# pc_healthypi_move_nRF5340_v4.net
KiCad netlist of a schematic drawn in EAGLE
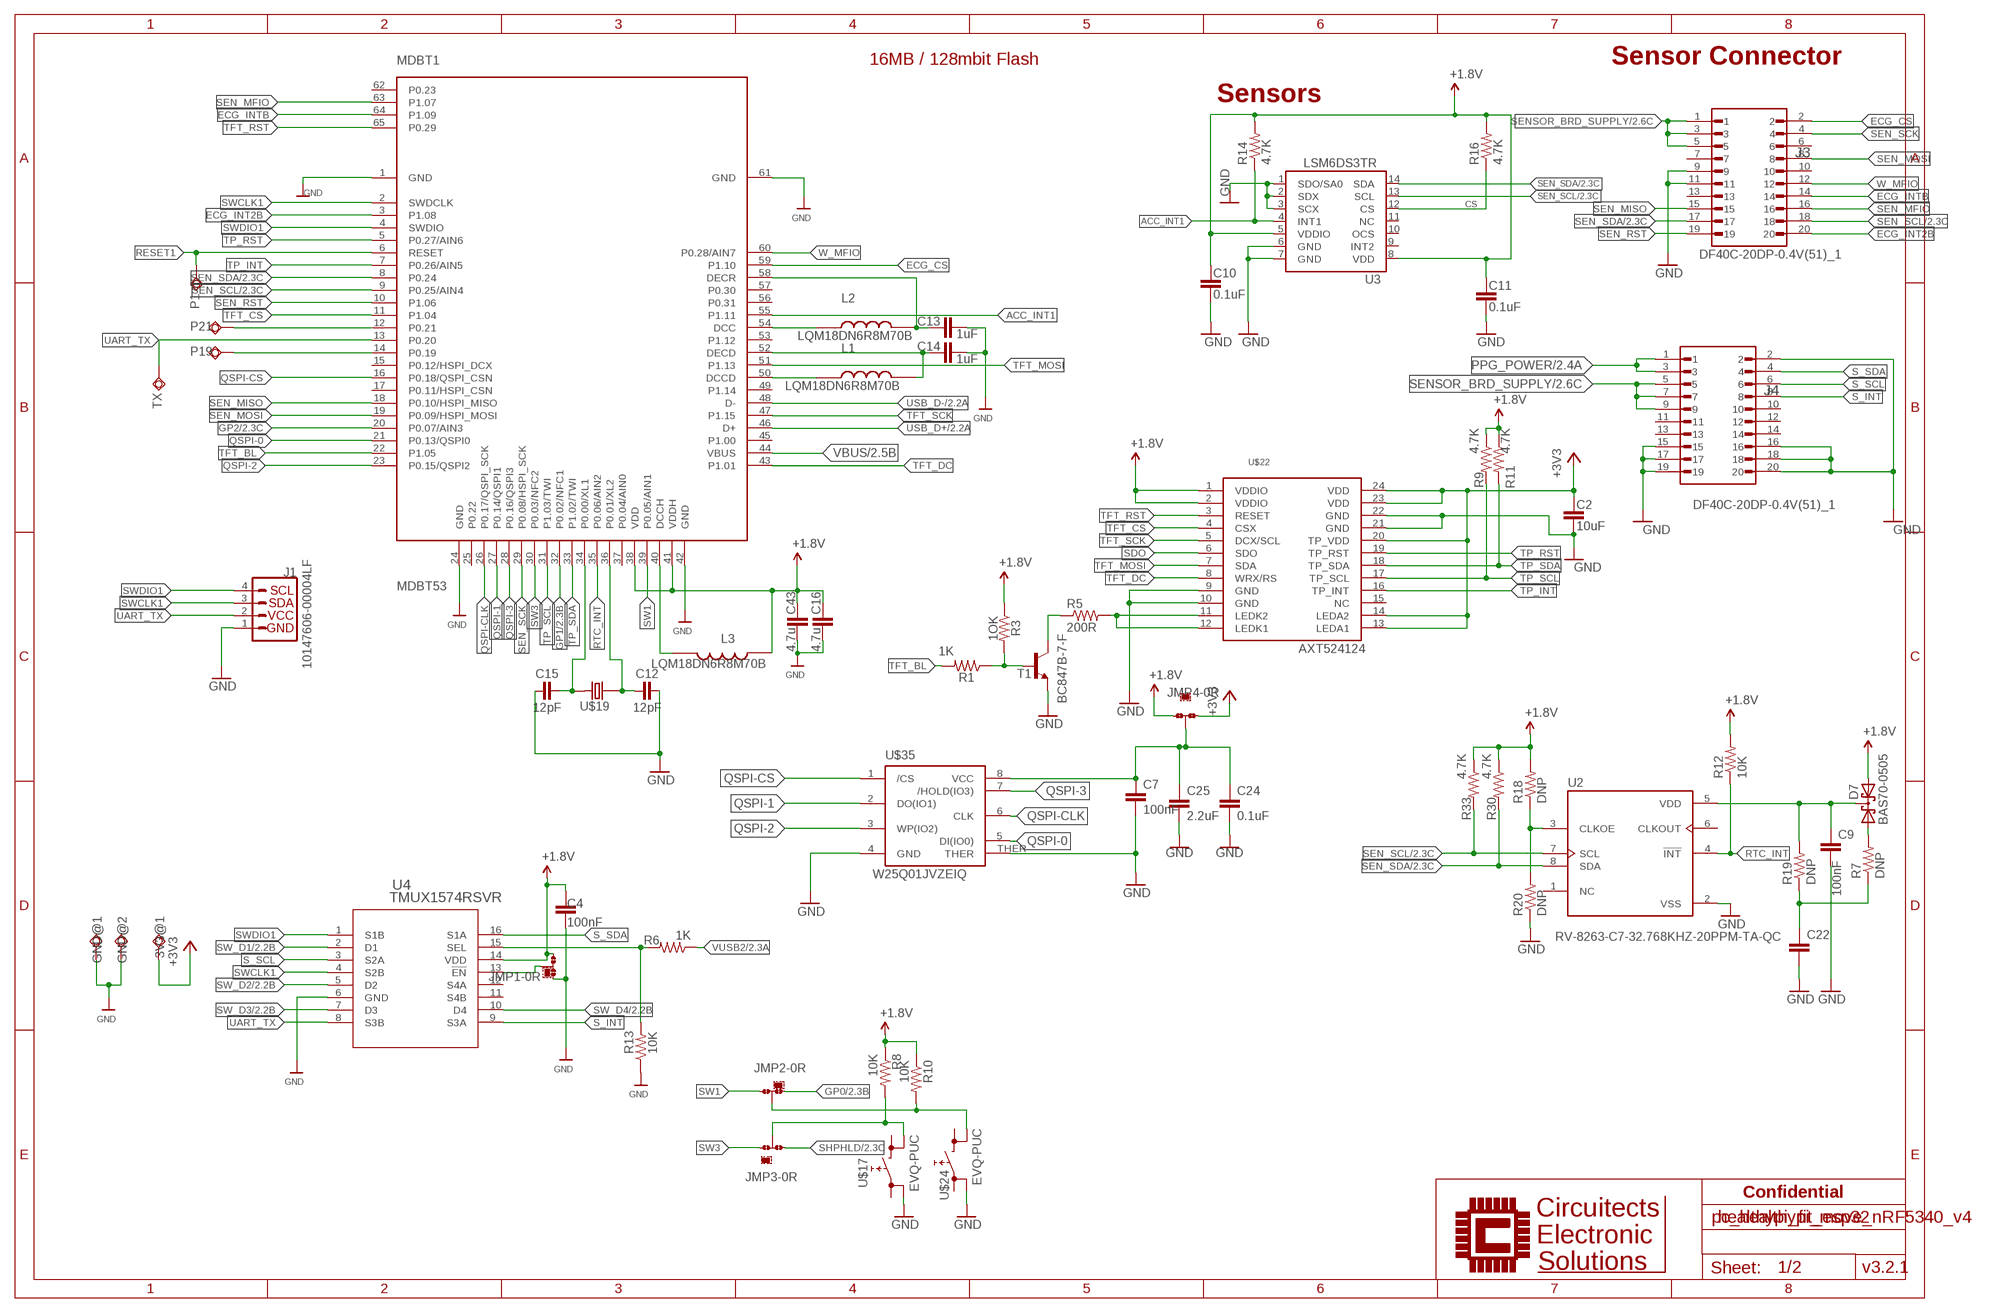
[diagram p0: schematic, sheet 1]
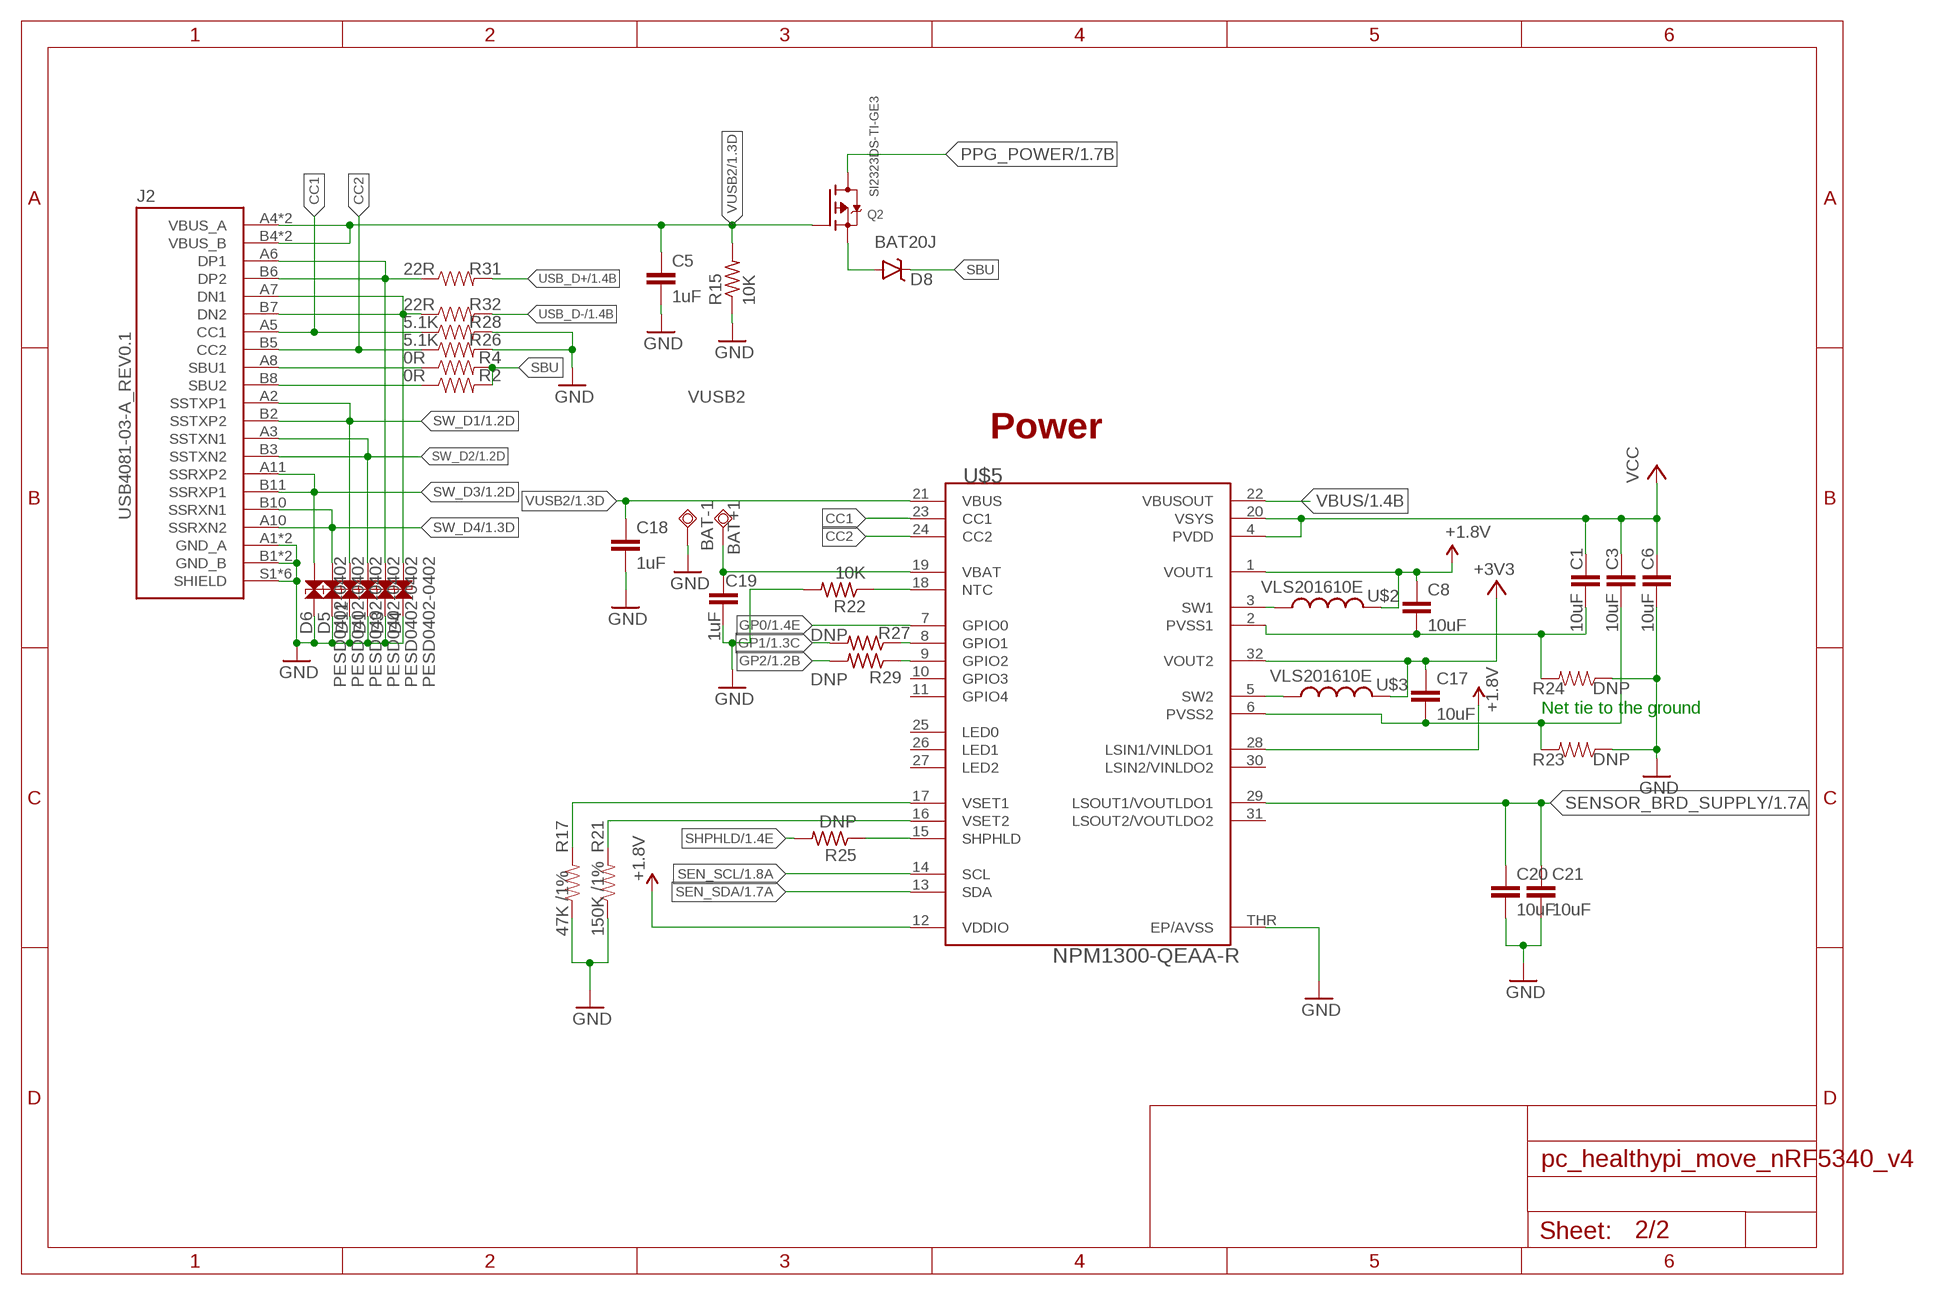
[diagram p1: schematic, sheet 2]

(export (version "E")
  (design (tool "Eeschema 10.0.6"))
  (components
    (comp (ref "BAT+1")
      (value "TPSQTP13SQ")
      (footprint "eagle-import:TP13SQ")
      (libsource (lib "eagle-import") (part "TPSQTP13SQ"))
    )
    (comp (ref "BAT-1")
      (value "TPSQTP13SQ")
      (footprint "eagle-import:TP13SQ")
      (libsource (lib "eagle-import") (part "TPSQTP13SQ"))
    )
    (comp (ref "C1")
      (value "10uF")
      (footprint "eagle-import:0402-TIGHT")
      (libsource (lib "eagle-import") (part "2.2UF-0402_TIGHT-10V-10%-X5R"))
    )
    (comp (ref "C3")
      (value "10uF")
      (footprint "eagle-import:0402-TIGHT")
      (libsource (lib "eagle-import") (part "2.2UF-0402_TIGHT-10V-10%-X5R"))
    )
    (comp (ref "C5")
      (value "1uF")
      (footprint "eagle-import:0402-TIGHT")
      (libsource (lib "eagle-import") (part "2.2UF-0402_TIGHT-10V-10%-X5R"))
    )
    (comp (ref "C6")
      (value "10uF")
      (footprint "eagle-import:0402-TIGHT")
      (libsource (lib "eagle-import") (part "2.2UF-0402_TIGHT-10V-10%-X5R"))
    )
    (comp (ref "C8")
      (value "10uF")
      (footprint "eagle-import:0402-TIGHT")
      (libsource (lib "eagle-import") (part "2.2UF-0402_TIGHT-10V-10%-X5R"))
    )
    (comp (ref "C17")
      (value "10uF")
      (footprint "eagle-import:0402-TIGHT")
      (libsource (lib "eagle-import") (part "2.2UF-0402_TIGHT-10V-10%-X5R"))
    )
    (comp (ref "C18")
      (value "1uF")
      (footprint "eagle-import:0402-TIGHT")
      (libsource (lib "eagle-import") (part "2.2UF-0402_TIGHT-10V-10%-X5R"))
    )
    (comp (ref "C19")
      (value "1uF")
      (footprint "eagle-import:0402-TIGHT")
      (libsource (lib "eagle-import") (part "2.2UF-0402_TIGHT-10V-10%-X5R"))
    )
    (comp (ref "C20")
      (value "10uF")
      (footprint "eagle-import:0402-TIGHT")
      (libsource (lib "eagle-import") (part "2.2UF-0402_TIGHT-10V-10%-X5R"))
    )
    (comp (ref "C21")
      (value "10uF")
      (footprint "eagle-import:0402-TIGHT")
      (libsource (lib "eagle-import") (part "2.2UF-0402_TIGHT-10V-10%-X5R"))
    )
    (comp (ref "D1")
      (value "PESD0402-0402")
      (footprint "eagle-import:0402")
      (fields
        (field (name "DIGIKEY_PART") "PESD0402-140CT-ND")
        (field (name "MOUSE_PART") "650-PESD0402-140")
      )
      (libsource (lib "eagle-import") (part "PESD0402-0402"))
    )
    (comp (ref "D3")
      (value "PESD0402-0402")
      (footprint "eagle-import:0402")
      (fields
        (field (name "DIGIKEY_PART") "PESD0402-140CT-ND")
        (field (name "MOUSE_PART") "650-PESD0402-140")
      )
      (libsource (lib "eagle-import") (part "PESD0402-0402"))
    )
    (comp (ref "D4")
      (value "PESD0402-0402")
      (footprint "eagle-import:0402")
      (fields
        (field (name "DIGIKEY_PART") "PESD0402-140CT-ND")
        (field (name "MOUSE_PART") "650-PESD0402-140")
      )
      (libsource (lib "eagle-import") (part "PESD0402-0402"))
    )
    (comp (ref "D5")
      (value "PESD0402-0402")
      (footprint "eagle-import:0402")
      (fields
        (field (name "DIGIKEY_PART") "PESD0402-140CT-ND")
        (field (name "MOUSE_PART") "650-PESD0402-140")
      )
      (libsource (lib "eagle-import") (part "PESD0402-0402"))
    )
    (comp (ref "D6")
      (value "PESD0402-0402")
      (footprint "eagle-import:0402")
      (fields
        (field (name "DIGIKEY_PART") "PESD0402-140CT-ND")
        (field (name "MOUSE_PART") "650-PESD0402-140")
      )
      (libsource (lib "eagle-import") (part "PESD0402-0402"))
    )
    (comp (ref "D8")
      (value "BAT20J")
      (footprint "eagle-import:SOD-323")
      (libsource (lib "eagle-import") (part "DIODE-SCHOTTKY-BAT20J"))
    )
    (comp (ref "D11")
      (value "PESD0402-0402")
      (footprint "eagle-import:0402")
      (fields
        (field (name "DIGIKEY_PART") "PESD0402-140CT-ND")
        (field (name "MOUSE_PART") "650-PESD0402-140")
      )
      (libsource (lib "eagle-import") (part "PESD0402-0402"))
    )
    (comp (ref "J2")
      (value "USB4081-03-A_REV0.1")
      (footprint "eagle-import:GCT_USB4081-03-A_REV0.1")
      (fields (field (name "MF") "Global Connector Technology") (field (name "MP") "USB4081-03-A"))
      (libsource (lib "eagle-import") (part "USB4081-03-A_REV0.1"))
    )
    (comp (ref "Q2")
      (value "SI2323DS-TI-GE3")
      (footprint "eagle-import:SOT23-R")
      (libsource (lib "eagle-import") (part "MOSFET-P"))
    )
    (comp (ref "R2")
      (value "0R")
      (footprint "eagle-import:0402-RES")
      (libsource (lib "eagle-import") (part "RESISTOR0402-RES"))
    )
    (comp (ref "R4")
      (value "0R")
      (footprint "eagle-import:0402-RES")
      (libsource (lib "eagle-import") (part "RESISTOR0402-RES"))
    )
    (comp (ref "R15")
      (value "10K")
      (footprint "eagle-import:R0402")
      (libsource (lib "eagle-import") (part "R-US_R0402"))
    )
    (comp (ref "R17")
      (value "47K /1%")
      (footprint "eagle-import:0402-RES")
      (libsource (lib "eagle-import") (part "RESISTOR0402-RES"))
    )
    (comp (ref "R21")
      (value "150K /1%")
      (footprint "eagle-import:0402-RES")
      (libsource (lib "eagle-import") (part "RESISTOR0402-RES"))
    )
    (comp (ref "R22")
      (value "10K")
      (footprint "eagle-import:R0402")
      (libsource (lib "eagle-import") (part "R-US_R0402"))
    )
    (comp (ref "R23")
      (value "DNP")
      (footprint "eagle-import:0402-RES")
      (libsource (lib "eagle-import") (part "RESISTOR0402-RES"))
    )
    (comp (ref "R24")
      (value "DNP")
      (footprint "eagle-import:0402-RES")
      (libsource (lib "eagle-import") (part "RESISTOR0402-RES"))
    )
    (comp (ref "R25")
      (value "DNP")
      (footprint "eagle-import:R0402")
      (libsource (lib "eagle-import") (part "R-US_R0402"))
    )
    (comp (ref "R26")
      (value "5.1K")
      (footprint "eagle-import:0402-RES")
      (libsource (lib "eagle-import") (part "RESISTOR0402-RES"))
    )
    (comp (ref "R27")
      (value "DNP")
      (footprint "eagle-import:R0402")
      (libsource (lib "eagle-import") (part "R-US_R0402"))
    )
    (comp (ref "R28")
      (value "5.1K")
      (footprint "eagle-import:0402-RES")
      (libsource (lib "eagle-import") (part "RESISTOR0402-RES"))
    )
    (comp (ref "R29")
      (value "DNP")
      (footprint "eagle-import:R0402")
      (libsource (lib "eagle-import") (part "R-US_R0402"))
    )
    (comp (ref "R31")
      (value "22R")
      (footprint "eagle-import:0402-RES")
      (libsource (lib "eagle-import") (part "RESISTOR0402-RES"))
    )
    (comp (ref "R32")
      (value "22R")
      (footprint "eagle-import:0402-RES")
      (libsource (lib "eagle-import") (part "RESISTOR0402-RES"))
    )
    (comp (ref "U$2")
      (value "VLS201610E")
      (footprint "eagle-import:VLS201610E")
      (libsource (lib "eagle-import") (part "VLS201610E"))
    )
    (comp (ref "U$3")
      (value "VLS201610E")
      (footprint "eagle-import:VLS201610E")
      (libsource (lib "eagle-import") (part "VLS201610E"))
    )
    (comp (ref "U$5")
      (value "NPM1300-QEAA-R")
      (footprint "eagle-import:PWQFN-32")
      (libsource (lib "eagle-import") (part "NPM1300-QEAA-R"))
    )
    (comp (ref "3V3@1")
      (value "TPSQTP13SQ")
      (footprint "eagle-import:TP13SQ")
      (libsource (lib "eagle-import") (part "TPSQTP13SQ"))
    )
    (comp (ref "C2")
      (value "10uF")
      (footprint "eagle-import:0603@1")
      (libsource (lib "eagle-import") (part "0.1UF-0603-100V-10%"))
    )
    (comp (ref "C4")
      (value "100nF")
      (footprint "eagle-import:0402-TIGHT")
      (libsource (lib "eagle-import") (part "2.2UF-0402_TIGHT-10V-10%-X5R"))
    )
    (comp (ref "C7")
      (value "100nF")
      (footprint "eagle-import:C0402")
      (libsource (lib "eagle-import") (part "C-EUC0402"))
    )
    (comp (ref "C9")
      (value "100nF")
      (footprint "eagle-import:C0402")
      (libsource (lib "eagle-import") (part "C-EUC0402"))
    )
    (comp (ref "C10")
      (value "0.1uF")
      (footprint "eagle-import:0402-TIGHT")
      (libsource (lib "eagle-import") (part "0.1UF-0402T-6.3V-10%-X7R"))
    )
    (comp (ref "C11")
      (value "0.1uF")
      (footprint "eagle-import:0402-TIGHT")
      (libsource (lib "eagle-import") (part "0.1UF-0402T-6.3V-10%-X7R"))
    )
    (comp (ref "C12")
      (value "12pF")
      (footprint "eagle-import:C0402")
      (libsource (lib "eagle-import") (part "CAPACITORS-0402"))
    )
    (comp (ref "C13")
      (value "1uF")
      (footprint "eagle-import:0402-TIGHT")
      (libsource (lib "eagle-import") (part "2.2UF-0402_TIGHT-10V-10%-X5R"))
    )
    (comp (ref "C14")
      (value "1uF")
      (footprint "eagle-import:0402-TIGHT")
      (libsource (lib "eagle-import") (part "2.2UF-0402_TIGHT-10V-10%-X5R"))
    )
    (comp (ref "C15")
      (value "12pF")
      (footprint "eagle-import:C0402")
      (libsource (lib "eagle-import") (part "CAPACITORS-0402"))
    )
    (comp (ref "C16")
      (value "4.7u")
      (footprint "eagle-import:C0402")
      (libsource (lib "eagle-import") (part "C-EUC0402"))
    )
    (comp (ref "C22")
      (value "C-EUC1210")
      (footprint "eagle-import:C1210")
      (libsource (lib "eagle-import") (part "C-EUC1210"))
    )
    (comp (ref "C24")
      (value "0.1uF")
      (footprint "eagle-import:0402-TIGHT")
      (libsource (lib "eagle-import") (part "0.1UF-0402T-6.3V-10%-X7R"))
    )
    (comp (ref "C25")
      (value "2.2uF")
      (footprint "eagle-import:0402-TIGHT")
      (libsource (lib "eagle-import") (part "2.2UF-0402_TIGHT-10V-10%-X5R"))
    )
    (comp (ref "C43")
      (value "4.7u")
      (footprint "eagle-import:C0402")
      (libsource (lib "eagle-import") (part "C-EUC0402"))
    )
    (comp (ref "D7")
      (value "BAS70-0505")
      (footprint "eagle-import:SOT23")
      (fields (field (name "MF") "Diotec") (field (name "MP") "BAS70-05"))
      (libsource (lib "eagle-import") (part "BAS70-0505"))
    )
    (comp (ref "GND@1")
      (value "TPSQTP13SQ")
      (footprint "eagle-import:TP13SQ")
      (libsource (lib "eagle-import") (part "TPSQTP13SQ"))
    )
    (comp (ref "GND@2")
      (value "TPSQTP13SQ")
      (footprint "eagle-import:TP13SQ")
      (libsource (lib "eagle-import") (part "TPSQTP13SQ"))
    )
    (comp (ref "J1")
      (value "10147606-00004LF")
      (footprint "eagle-import:JST04_1MM_RA")
      (libsource (lib "eagle-import") (part "QWIIC_CONNECTORJS-1MM"))
    )
    (comp (ref "J3")
      (value "DF40C-20DP-0.4V(51)_1")
      (footprint "eagle-import:HRS_DF40C-20DP-0.4V(51)")
      (fields (field (name "MANUFACTURER") "Hirose Electric"))
      (libsource (lib "eagle-import") (part "DF40C-20DP-0.4V(51)_1"))
    )
    (comp (ref "J4")
      (value "DF40C-20DP-0.4V(51)_1")
      (footprint "eagle-import:HRS_DF40C-20DP-0.4V(51)")
      (fields (field (name "MANUFACTURER") "Hirose Electric"))
      (libsource (lib "eagle-import") (part "DF40C-20DP-0.4V(51)_1"))
    )
    (comp (ref "JMP1")
      (value "0R-JUMPB")
      (footprint "eagle-import:B0R-JMP")
      (libsource (lib "eagle-import") (part "0R-JUMPB"))
    )
    (comp (ref "JMP2")
      (value "0R-JUMPB")
      (footprint "eagle-import:B0R-JMP")
      (libsource (lib "eagle-import") (part "0R-JUMPB"))
    )
    (comp (ref "JMP3")
      (value "0R-JUMPB")
      (footprint "eagle-import:B0R-JMP")
      (libsource (lib "eagle-import") (part "0R-JUMPB"))
    )
    (comp (ref "JMP4")
      (value "0R-JUMPB")
      (footprint "eagle-import:B0R-JMP")
      (libsource (lib "eagle-import") (part "0R-JUMPB"))
    )
    (comp (ref "L1")
      (value "LQM18DN6R8M70B")
      (footprint "eagle-import:INDC1608X95N")
      (fields (field (name "MF") "Murata"))
      (libsource (lib "eagle-import") (part "LQM18DN6R8M70B"))
    )
    (comp (ref "L2")
      (value "LQM18DN6R8M70B")
      (footprint "eagle-import:INDC1608X95N")
      (fields (field (name "MF") "Murata"))
      (libsource (lib "eagle-import") (part "LQM18DN6R8M70B"))
    )
    (comp (ref "L3")
      (value "LQM18DN6R8M70B")
      (footprint "eagle-import:INDC1608X95N")
      (fields (field (name "MF") "Murata"))
      (libsource (lib "eagle-import") (part "LQM18DN6R8M70B"))
    )
    (comp (ref "MDBT1")
      (value "MDBT53")
      (footprint "eagle-import:MDBT53")
      (libsource (lib "eagle-import") (part "MDBT53"))
    )
    (comp (ref "P1")
      (value "TPSQTP13SQ")
      (footprint "eagle-import:TP13SQ")
      (libsource (lib "eagle-import") (part "TPSQTP13SQ"))
    )
    (comp (ref "P19")
      (value "TPSQTP13SQ")
      (footprint "eagle-import:TP13SQ")
      (libsource (lib "eagle-import") (part "TPSQTP13SQ"))
    )
    (comp (ref "P21")
      (value "TPSQTP13SQ")
      (footprint "eagle-import:TP13SQ")
      (libsource (lib "eagle-import") (part "TPSQTP13SQ"))
    )
    (comp (ref "R1")
      (value "200")
      (footprint "eagle-import:R0402")
      (libsource (lib "eagle-import") (part "R-US_R0402"))
    )
    (comp (ref "R3")
      (value "200")
      (footprint "eagle-import:R0402")
      (libsource (lib "eagle-import") (part "R-US_R0402"))
    )
    (comp (ref "R5")
      (value "200R")
      (footprint "eagle-import:R0402")
      (libsource (lib "eagle-import") (part "R-US_R0402"))
    )
    (comp (ref "R6")
      (value "1K")
      (footprint "eagle-import:0402-RES")
      (libsource (lib "eagle-import") (part "RESISTOR0402-RES"))
    )
    (comp (ref "R7")
      (value "DNP")
      (footprint "eagle-import:R0402")
      (libsource (lib "eagle-import") (part "R-US_R0402"))
    )
    (comp (ref "R8")
      (value "10K")
      (footprint "eagle-import:R0402")
      (libsource (lib "eagle-import") (part "R-US_R0402"))
    )
    (comp (ref "R9")
      (value "4.7K")
      (footprint "eagle-import:R0402")
      (libsource (lib "eagle-import") (part "R-US_R0402"))
    )
    (comp (ref "R10")
      (value "10K")
      (footprint "eagle-import:R0402")
      (libsource (lib "eagle-import") (part "R-US_R0402"))
    )
    (comp (ref "R11")
      (value "4.7K")
      (footprint "eagle-import:R0402")
      (libsource (lib "eagle-import") (part "R-US_R0402"))
    )
    (comp (ref "R12")
      (value "10K")
      (footprint "eagle-import:R0402")
      (libsource (lib "eagle-import") (part "R-US_R0402"))
    )
    (comp (ref "R13")
      (value "10K")
      (footprint "eagle-import:R0402")
      (libsource (lib "eagle-import") (part "R-US_R0402"))
    )
    (comp (ref "R14")
      (value "4.7K")
      (footprint "eagle-import:R0402")
      (libsource (lib "eagle-import") (part "R-US_R0402"))
    )
    (comp (ref "R16")
      (value "4.7K")
      (footprint "eagle-import:R0402")
      (libsource (lib "eagle-import") (part "R-US_R0402"))
    )
    (comp (ref "R18")
      (value "DNP")
      (footprint "eagle-import:R0402")
      (libsource (lib "eagle-import") (part "R-US_R0402"))
    )
    (comp (ref "R19")
      (value "DNP")
      (footprint "eagle-import:R0402")
      (libsource (lib "eagle-import") (part "R-US_R0402"))
    )
    (comp (ref "R20")
      (value "DNP")
      (footprint "eagle-import:R0402")
      (libsource (lib "eagle-import") (part "R-US_R0402"))
    )
    (comp (ref "R30")
      (value "4.7K")
      (footprint "eagle-import:R0402")
      (libsource (lib "eagle-import") (part "R-US_R0402"))
    )
    (comp (ref "R33")
      (value "4.7K")
      (footprint "eagle-import:R0402")
      (libsource (lib "eagle-import") (part "R-US_R0402"))
    )
    (comp (ref "T1")
      (value "BC847B-7-F")
      (footprint "eagle-import:SOT23-BEC")
      (libsource (lib "eagle-import") (part "-NPN-SOT23-BECMMBT2222ALT1"))
    )
    (comp (ref "TX")
      (value "TPSQTP13SQ")
      (footprint "eagle-import:TP13SQ")
      (libsource (lib "eagle-import") (part "TPSQTP13SQ"))
    )
    (comp (ref "U$17")
      (value "EVQ-PUC")
      (footprint "eagle-import:EVQ-PUC")
      (libsource (lib "eagle-import") (part "EVQ-PUC"))
    )
    (comp (ref "U$19")
      (value "520-327-12.5-34B(32.768KHZ)")
      (footprint "eagle-import:ECX-31B")
      (libsource (lib "eagle-import") (part "ECS-X-34B"))
    )
    (comp (ref "U$22")
      (value "AXT524124")
      (footprint "eagle-import:AXT524124")
      (libsource (lib "eagle-import") (part "AXT524124"))
    )
    (comp (ref "U$24")
      (value "EVQ-PUC")
      (footprint "eagle-import:EVQ-PUC")
      (libsource (lib "eagle-import") (part "EVQ-PUC"))
    )
    (comp (ref "U$35")
      (value "W25Q01JVZEIQ")
      (footprint "eagle-import:WSON-08")
      (libsource (lib "eagle-import") (part "W25N01GVZEIG"))
    )
    (comp (ref "U2")
      (value "RV-8263-C7-32.768KHZ-20PPM-TA-QC")
      (footprint "eagle-import:IC_RV-8263-C7-32.768KHZ-20PPM-TA-QC")
      (fields (field (name "MF") "Micro Crystal"))
      (libsource (lib "eagle-import") (part "RV-8263-C7-32.768KHZ-20PPM-TA-QC"))
    )
    (comp (ref "U3")
      (value "LSM6DS3TR")
      (footprint "eagle-import:LGA14L")
      (libsource (lib "eagle-import") (part "LSM6DS3"))
    )
    (comp (ref "U4")
      (value "TMUX1574RSVR")
      (footprint "eagle-import:RSV16_TEX")
      (fields (field (name "COPYRIGHT") "Copyright (C) 2024 Ultra Librarian. All rights reserved."))
      (libsource (lib "eagle-import") (part "TMUX1574RSVR"))
    )
  )
  (nets
    (net (code "1") (name "+1.8V") (class "Default")
      (node (ref "C10") (pin "1") (pinfunction "1_1") (pintype "passive"))
      (node (ref "C11") (pin "1") (pinfunction "1_1") (pintype "passive"))
      (node (ref "C16") (pin "1") (pinfunction "1_1") (pintype "passive"))
      (node (ref "C4") (pin "1") (pinfunction "1_1") (pintype "passive"))
      (node (ref "C43") (pin "1") (pinfunction "1_1") (pintype "passive"))
      (node (ref "C8") (pin "1") (pinfunction "1_1") (pintype "passive"))
      (node (ref "D7") (pin "2") (pinfunction "A2_2") (pintype "passive"))
      (node (ref "JMP1") (pin "3") (pinfunction "3_3") (pintype "passive"))
      (node (ref "JMP4") (pin "3") (pinfunction "3_3") (pintype "passive"))
      (node (ref "L3") (pin "1") (pinfunction "1_1") (pintype "passive"))
      (node (ref "MDBT1") (pin "38") (pinfunction "VDD_38") (pintype "bidirectional"))
      (node (ref "MDBT1") (pin "41") (pinfunction "VDDH_41") (pintype "bidirectional"))
      (node (ref "R10") (pin "1") (pinfunction "1_1") (pintype "passive"))
      (node (ref "R11") (pin "1") (pinfunction "1_1") (pintype "passive"))
      (node (ref "R12") (pin "2") (pinfunction "2_2") (pintype "passive"))
      (node (ref "R14") (pin "2") (pinfunction "2_2") (pintype "passive"))
      (node (ref "R16") (pin "2") (pinfunction "2_2") (pintype "passive"))
      (node (ref "R18") (pin "2") (pinfunction "2_2") (pintype "passive"))
      (node (ref "R3") (pin "1") (pinfunction "1_1") (pintype "passive"))
      (node (ref "R30") (pin "1") (pinfunction "1_1") (pintype "passive"))
      (node (ref "R33") (pin "1") (pinfunction "1_1") (pintype "passive"))
      (node (ref "R8") (pin "1") (pinfunction "1_1") (pintype "passive"))
      (node (ref "R9") (pin "1") (pinfunction "1_1") (pintype "passive"))
      (node (ref "U$2") (pin "2") (pinfunction "2_2") (pintype "passive"))
      (node (ref "U$22") (pin "1") (pinfunction "VDDIO_1") (pintype "bidirectional"))
      (node (ref "U$22") (pin "2") (pinfunction "VDDIO_2") (pintype "bidirectional"))
      (node (ref "U$5") (pin "1") (pinfunction "VOUT1_1") (pintype "bidirectional"))
      (node (ref "U$5") (pin "12") (pinfunction "VDDIO_12") (pintype "bidirectional"))
      (node (ref "U$5") (pin "28") (pinfunction "LSIN1/VINLDO1_28") (pintype "bidirectional"))
      (node (ref "U3") (pin "5") (pinfunction "VDDIO_5") (pintype "bidirectional"))
      (node (ref "U3") (pin "8") (pinfunction "VDD_8") (pintype "bidirectional"))
      (node (ref "U4") (pin "14") (pinfunction "VDD_14") (pintype "power_in"))
    )
    (net (code "2") (name "+3V3") (class "Default")
      (node (ref "3V3@1") (pin "TP") (pinfunction "TP_TP") (pintype "input"))
      (node (ref "C17") (pin "1") (pinfunction "1_1") (pintype "passive"))
      (node (ref "C2") (pin "1") (pinfunction "1_1") (pintype "passive"))
      (node (ref "JMP4") (pin "1") (pinfunction "1_1") (pintype "passive"))
      (node (ref "U$22") (pin "13") (pinfunction "LEDA1_13") (pintype "bidirectional"))
      (node (ref "U$22") (pin "14") (pinfunction "LEDA2_14") (pintype "bidirectional"))
      (node (ref "U$22") (pin "20") (pinfunction "TP_VDD_20") (pintype "bidirectional"))
      (node (ref "U$22") (pin "23") (pinfunction "VDD_23") (pintype "bidirectional"))
      (node (ref "U$22") (pin "24") (pinfunction "VDD_24") (pintype "bidirectional"))
      (node (ref "U$3") (pin "2") (pinfunction "2_2") (pintype "passive"))
      (node (ref "U$5") (pin "32") (pinfunction "VOUT2_32") (pintype "bidirectional"))
    )
    (net (code "3") (name "ACC_INT1") (class "Default")
      (node (ref "MDBT1") (pin "55") (pinfunction "P1.11_55") (pintype "bidirectional"))
      (node (ref "R14") (pin "1") (pinfunction "1_1") (pintype "passive"))
      (node (ref "U3") (pin "4") (pinfunction "INT1_4") (pintype "bidirectional"))
    )
    (net (code "4") (name "CC1") (class "Default")
      (node (ref "J2") (pin "A5") (pinfunction "CC1_A5") (pintype "bidirectional"))
      (node (ref "R28") (pin "1") (pinfunction "1_1") (pintype "passive"))
      (node (ref "U$5") (pin "23") (pinfunction "CC1_23") (pintype "bidirectional"))
    )
    (net (code "5") (name "CC2") (class "Default")
      (node (ref "J2") (pin "B5") (pinfunction "CC2_B5") (pintype "bidirectional"))
      (node (ref "R26") (pin "1") (pinfunction "1_1") (pintype "passive"))
      (node (ref "U$5") (pin "24") (pinfunction "CC2_24") (pintype "bidirectional"))
    )
    (net (code "6") (name "CS") (class "Default")
      (node (ref "R16") (pin "1") (pinfunction "1_1") (pintype "passive"))
      (node (ref "U3") (pin "12") (pinfunction "CS_12") (pintype "bidirectional"))
    )
    (net (code "7") (name "ECG_CS") (class "Default")
      (node (ref "J3") (pin "2") (pinfunction "2_2") (pintype "passive"))
      (node (ref "MDBT1") (pin "59") (pinfunction "P1.10_59") (pintype "bidirectional"))
    )
    (net (code "8") (name "ECG_INT2B") (class "Default")
      (node (ref "J3") (pin "20") (pinfunction "20_20") (pintype "passive"))
      (node (ref "MDBT1") (pin "3") (pinfunction "P1.08_3") (pintype "bidirectional"))
    )
    (net (code "9") (name "ECG_INTB") (class "Default")
      (node (ref "J3") (pin "14") (pinfunction "14_14") (pintype "passive"))
      (node (ref "MDBT1") (pin "64") (pinfunction "P1.09_64") (pintype "bidirectional"))
    )
    (net (code "10") (name "GND") (class "Default")
      (node (ref "BAT-1") (pin "TP") (pinfunction "TP_TP") (pintype "input"))
      (node (ref "C10") (pin "2") (pinfunction "2_2") (pintype "passive"))
      (node (ref "C11") (pin "2") (pinfunction "2_2") (pintype "passive"))
      (node (ref "C12") (pin "2") (pinfunction "2_2") (pintype "passive"))
      (node (ref "C13") (pin "2") (pinfunction "2_2") (pintype "passive"))
      (node (ref "C14") (pin "2") (pinfunction "2_2") (pintype "passive"))
      (node (ref "C15") (pin "1") (pinfunction "1_1") (pintype "passive"))
      (node (ref "C16") (pin "2") (pinfunction "2_2") (pintype "passive"))
      (node (ref "C18") (pin "2") (pinfunction "2_2") (pintype "passive"))
      (node (ref "C19") (pin "2") (pinfunction "2_2") (pintype "passive"))
      (node (ref "C2") (pin "2") (pinfunction "2_2") (pintype "passive"))
      (node (ref "C20") (pin "2") (pinfunction "2_2") (pintype "passive"))
      (node (ref "C21") (pin "2") (pinfunction "2_2") (pintype "passive"))
      (node (ref "C22") (pin "2") (pinfunction "2_2") (pintype "passive"))
      (node (ref "C24") (pin "2") (pinfunction "2_2") (pintype "passive"))
      (node (ref "C25") (pin "2") (pinfunction "2_2") (pintype "passive"))
      (node (ref "C4") (pin "2") (pinfunction "2_2") (pintype "passive"))
      (node (ref "C43") (pin "2") (pinfunction "2_2") (pintype "passive"))
      (node (ref "C5") (pin "2") (pinfunction "2_2") (pintype "passive"))
      (node (ref "C6") (pin "2") (pinfunction "2_2") (pintype "passive"))
      (node (ref "C7") (pin "2") (pinfunction "2_2") (pintype "passive"))
      (node (ref "C9") (pin "2") (pinfunction "2_2") (pintype "passive"))
      (node (ref "D1") (pin "1") (pinfunction "1_1") (pintype "bidirectional"))
      (node (ref "D11") (pin "1") (pinfunction "1_1") (pintype "bidirectional"))
      (node (ref "D3") (pin "1") (pinfunction "1_1") (pintype "bidirectional"))
      (node (ref "D4") (pin "1") (pinfunction "1_1") (pintype "bidirectional"))
      (node (ref "D5") (pin "1") (pinfunction "1_1") (pintype "bidirectional"))
      (node (ref "D6") (pin "1") (pinfunction "1_1") (pintype "bidirectional"))
      (node (ref "GND@1") (pin "TP") (pinfunction "TP_TP") (pintype "input"))
      (node (ref "GND@2") (pin "TP") (pinfunction "TP_TP") (pintype "input"))
      (node (ref "J1") (pin "1") (pinfunction "1_1") (pintype "power_in"))
      (node (ref "J2") (pin "A1") (pinfunction "GND_A_A1") (pintype "power_in"))
      (node (ref "J2") (pin "A12") (pinfunction "GND_A_A12") (pintype "power_in"))
      (node (ref "J2") (pin "B1") (pinfunction "GND_B_B1") (pintype "power_in"))
      (node (ref "J2") (pin "B12") (pinfunction "GND_B_B12") (pintype "power_in"))
      (node (ref "J2") (pin "S1") (pinfunction "SHIELD_S1") (pintype "passive"))
      (node (ref "J2") (pin "S2") (pinfunction "SHIELD_S2") (pintype "passive"))
      (node (ref "J2") (pin "S3") (pinfunction "SHIELD_S3") (pintype "passive"))
      (node (ref "J2") (pin "S4") (pinfunction "SHIELD_S4") (pintype "passive"))
      (node (ref "J2") (pin "S5") (pinfunction "SHIELD_S5") (pintype "passive"))
      (node (ref "J2") (pin "S6") (pinfunction "SHIELD_S6") (pintype "passive"))
      (node (ref "J3") (pin "11") (pinfunction "11_11") (pintype "passive"))
      (node (ref "J3") (pin "9") (pinfunction "9_9") (pintype "passive"))
      (node (ref "J4") (pin "15") (pinfunction "15_15") (pintype "passive"))
      (node (ref "J4") (pin "16") (pinfunction "16_16") (pintype "passive"))
      (node (ref "J4") (pin "17") (pinfunction "17_17") (pintype "passive"))
      (node (ref "J4") (pin "18") (pinfunction "18_18") (pintype "passive"))
      (node (ref "J4") (pin "19") (pinfunction "19_19") (pintype "passive"))
      (node (ref "J4") (pin "2") (pinfunction "2_2") (pintype "passive"))
      (node (ref "J4") (pin "20") (pinfunction "20_20") (pintype "passive"))
      (node (ref "JMP1") (pin "1") (pinfunction "1_1") (pintype "passive"))
      (node (ref "MDBT1") (pin "1") (pinfunction "GND_1") (pintype "bidirectional"))
      (node (ref "MDBT1") (pin "24") (pinfunction "GND_24") (pintype "bidirectional"))
      (node (ref "MDBT1") (pin "42") (pinfunction "GND_42") (pintype "bidirectional"))
      (node (ref "MDBT1") (pin "61") (pinfunction "GND_61") (pintype "bidirectional"))
      (node (ref "R13") (pin "1") (pinfunction "1_1") (pintype "passive"))
      (node (ref "R15") (pin "1") (pinfunction "1_1") (pintype "passive"))
      (node (ref "R17") (pin "1") (pinfunction "1_1") (pintype "passive"))
      (node (ref "R20") (pin "1") (pinfunction "1_1") (pintype "passive"))
      (node (ref "R21") (pin "1") (pinfunction "1_1") (pintype "passive"))
      (node (ref "R22") (pin "2") (pinfunction "2_2") (pintype "passive"))
      (node (ref "R23") (pin "1") (pinfunction "1_1") (pintype "passive"))
      (node (ref "R24") (pin "1") (pinfunction "1_1") (pintype "passive"))
      (node (ref "R26") (pin "2") (pinfunction "2_2") (pintype "passive"))
      (node (ref "R28") (pin "2") (pinfunction "2_2") (pintype "passive"))
      (node (ref "T1") (pin "E") (pinfunction "E_E") (pintype "passive"))
      (node (ref "U$17") (pin "3") (pinfunction "0_3") (pintype "passive"))
      (node (ref "U$22") (pin "10") (pinfunction "GND_10") (pintype "bidirectional"))
      (node (ref "U$22") (pin "21") (pinfunction "GND_21") (pintype "bidirectional"))
      (node (ref "U$22") (pin "22") (pinfunction "GND_22") (pintype "bidirectional"))
      (node (ref "U$22") (pin "9") (pinfunction "GND_9") (pintype "bidirectional"))
      (node (ref "U$24") (pin "3") (pinfunction "0_3") (pintype "passive"))
      (node (ref "U$35") (pin "4") (pinfunction "GND_4") (pintype "bidirectional"))
      (node (ref "U$35") (pin "THER") (pinfunction "THER_THER") (pintype "bidirectional"))
      (node (ref "U$5") (pin "THR") (pinfunction "EP/AVSS_THR") (pintype "bidirectional"))
      (node (ref "U2") (pin "2") (pinfunction "VSS_2") (pintype "power_in"))
      (node (ref "U3") (pin "1") (pinfunction "SDO/SA0_1") (pintype "bidirectional"))
      (node (ref "U3") (pin "2") (pinfunction "SDX_2") (pintype "bidirectional"))
      (node (ref "U3") (pin "3") (pinfunction "SCX_3") (pintype "bidirectional"))
      (node (ref "U3") (pin "6") (pinfunction "GND_6") (pintype "bidirectional"))
      (node (ref "U3") (pin "7") (pinfunction "GND_7") (pintype "bidirectional"))
      (node (ref "U4") (pin "6") (pinfunction "GND_6") (pintype "passive"))
    )
    (net (code "11") (name "GP0") (class "Default")
      (node (ref "JMP2") (pin "1") (pinfunction "1_1") (pintype "passive"))
      (node (ref "U$5") (pin "7") (pinfunction "GPIO0_7") (pintype "bidirectional"))
    )
    (net (code "12") (name "GP1") (class "Default")
      (node (ref "MDBT1") (pin "32") (pinfunction "P0.02/NFC1_32") (pintype "bidirectional"))
      (node (ref "R27") (pin "2") (pinfunction "2_2") (pintype "passive"))
    )
    (net (code "13") (name "GP2") (class "Default")
      (node (ref "MDBT1") (pin "20") (pinfunction "P0.07/AIN3_20") (pintype "bidirectional"))
      (node (ref "R29") (pin "2") (pinfunction "2_2") (pintype "passive"))
    )
    (net (code "14") (name "Net-(C22-Pad1)") (class "Default")
      (node (ref "C22") (pin "1") (pinfunction "1_1") (pintype "passive"))
      (node (ref "R19") (pin "1") (pinfunction "1_1") (pintype "passive"))
      (node (ref "R7") (pin "1") (pinfunction "1_1") (pintype "passive"))
    )
    (net (code "15") (name "Net-(D7-A1)") (class "Default")
      (node (ref "D7") (pin "1") (pinfunction "A1_1") (pintype "passive"))
      (node (ref "R7") (pin "2") (pinfunction "2_2") (pintype "passive"))
    )
    (net (code "16") (name "Net-(D7-K1K2)") (class "Default")
      (node (ref "C9") (pin "1") (pinfunction "1_1") (pintype "passive"))
      (node (ref "D7") (pin "3") (pinfunction "K1K2_3") (pintype "passive"))
      (node (ref "R19") (pin "2") (pinfunction "2_2") (pintype "passive"))
      (node (ref "U2") (pin "5") (pinfunction "VDD_5") (pintype "power_in"))
    )
    (net (code "17") (name "Net-(J2-DN1)") (class "Default")
      (node (ref "D4") (pin "2") (pinfunction "2_2") (pintype "bidirectional"))
      (node (ref "J2") (pin "A7") (pinfunction "DN1_A7") (pintype "bidirectional"))
      (node (ref "J2") (pin "B7") (pinfunction "DN2_B7") (pintype "bidirectional"))
      (node (ref "R32") (pin "1") (pinfunction "1_1") (pintype "passive"))
    )
    (net (code "18") (name "Net-(J2-DP1)") (class "Default")
      (node (ref "D3") (pin "2") (pinfunction "2_2") (pintype "bidirectional"))
      (node (ref "J2") (pin "A6") (pinfunction "DP1_A6") (pintype "bidirectional"))
      (node (ref "J2") (pin "B6") (pinfunction "DP2_B6") (pintype "bidirectional"))
      (node (ref "R31") (pin "1") (pinfunction "1_1") (pintype "passive"))
    )
    (net (code "19") (name "Net-(J2-SBU1)") (class "Default")
      (node (ref "J2") (pin "A8") (pinfunction "SBU1_A8") (pintype "bidirectional"))
      (node (ref "R4") (pin "1") (pinfunction "1_1") (pintype "passive"))
    )
    (net (code "20") (name "Net-(J2-SBU2)") (class "Default")
      (node (ref "J2") (pin "B8") (pinfunction "SBU2_B8") (pintype "bidirectional"))
      (node (ref "R2") (pin "1") (pinfunction "1_1") (pintype "passive"))
    )
    (net (code "21") (name "Net-(JMP2-Pad2)") (class "Default")
      (node (ref "JMP2") (pin "2") (pinfunction "2_2") (pintype "passive"))
      (node (ref "R10") (pin "2") (pinfunction "2_2") (pintype "passive"))
      (node (ref "U$24") (pin "2") (pinfunction "1_2") (pintype "passive"))
    )
    (net (code "22") (name "Net-(JMP3-Pad2)") (class "Default")
      (node (ref "JMP3") (pin "2") (pinfunction "2_2") (pintype "passive"))
      (node (ref "R8") (pin "2") (pinfunction "2_2") (pintype "passive"))
      (node (ref "U$17") (pin "2") (pinfunction "1_2") (pintype "passive"))
    )
    (net (code "23") (name "Net-(MDBT1-DCC)") (class "Default")
      (node (ref "L2") (pin "1") (pinfunction "1_1") (pintype "passive"))
      (node (ref "MDBT1") (pin "54") (pinfunction "DCC_54") (pintype "bidirectional"))
    )
    (net (code "24") (name "Net-(MDBT1-DCCD)") (class "Default")
      (node (ref "L1") (pin "1") (pinfunction "1_1") (pintype "passive"))
      (node (ref "MDBT1") (pin "50") (pinfunction "DCCD_50") (pintype "bidirectional"))
    )
    (net (code "25") (name "Net-(MDBT1-DCCH)") (class "Default")
      (node (ref "L3") (pin "2") (pinfunction "2_2") (pintype "passive"))
      (node (ref "MDBT1") (pin "40") (pinfunction "DCCH_40") (pintype "bidirectional"))
    )
    (net (code "26") (name "Net-(MDBT1-DECD)") (class "Default")
      (node (ref "C14") (pin "1") (pinfunction "1_1") (pintype "passive"))
      (node (ref "L1") (pin "2") (pinfunction "2_2") (pintype "passive"))
      (node (ref "MDBT1") (pin "52") (pinfunction "DECD_52") (pintype "bidirectional"))
    )
    (net (code "27") (name "Net-(MDBT1-DECR)") (class "Default")
      (node (ref "C13") (pin "1") (pinfunction "1_1") (pintype "passive"))
      (node (ref "L2") (pin "2") (pinfunction "2_2") (pintype "passive"))
      (node (ref "MDBT1") (pin "58") (pinfunction "DECR_58") (pintype "bidirectional"))
    )
    (net (code "28") (name "Net-(MDBT1-P0.00{slash}XL1)") (class "Default")
      (node (ref "C15") (pin "2") (pinfunction "2_2") (pintype "passive"))
      (node (ref "MDBT1") (pin "34") (pinfunction "P0.00/XL1_34") (pintype "bidirectional"))
      (node (ref "U$19") (pin "P$2") (pinfunction "2_P$2") (pintype "passive"))
    )
    (net (code "29") (name "Net-(MDBT1-P0.01{slash}XL2)") (class "Default")
      (node (ref "C12") (pin "1") (pinfunction "1_1") (pintype "passive"))
      (node (ref "MDBT1") (pin "36") (pinfunction "P0.01/XL2_36") (pintype "bidirectional"))
      (node (ref "U$19") (pin "P$1") (pinfunction "1_P$1") (pintype "passive"))
    )
    (net (code "30") (name "Net-(MDBT1-P0.19)") (class "Default")
      (node (ref "MDBT1") (pin "14") (pinfunction "P0.19_14") (pintype "bidirectional"))
      (node (ref "P19") (pin "TP") (pinfunction "TP_TP") (pintype "input"))
    )
    (net (code "31") (name "Net-(MDBT1-P0.21)") (class "Default")
      (node (ref "MDBT1") (pin "12") (pinfunction "P0.21_12") (pintype "bidirectional"))
      (node (ref "P21") (pin "TP") (pinfunction "TP_TP") (pintype "input"))
    )
    (net (code "32") (name "Net-(Q2-S)") (class "Default")
      (node (ref "D8") (pin "A") (pinfunction "A_A") (pintype "passive"))
      (node (ref "Q2") (pin "2") (pinfunction "S_2") (pintype "passive"))
    )
    (net (code "33") (name "Net-(R1-Pad1)") (class "Default")
      (node (ref "R1") (pin "1") (pinfunction "1_1") (pintype "passive"))
      (node (ref "R3") (pin "2") (pinfunction "2_2") (pintype "passive"))
      (node (ref "T1") (pin "B") (pinfunction "B_B") (pintype "passive"))
    )
    (net (code "34") (name "Net-(R5-Pad1)") (class "Default")
      (node (ref "R5") (pin "1") (pinfunction "1_1") (pintype "passive"))
      (node (ref "T1") (pin "C") (pinfunction "C_C") (pintype "passive"))
    )
    (net (code "35") (name "Net-(U$5-GPIO1)") (class "Default")
      (node (ref "R27") (pin "1") (pinfunction "1_1") (pintype "passive"))
      (node (ref "U$5") (pin "8") (pinfunction "GPIO1_8") (pintype "bidirectional"))
    )
    (net (code "36") (name "Net-(U$5-GPIO2)") (class "Default")
      (node (ref "R29") (pin "1") (pinfunction "1_1") (pintype "passive"))
      (node (ref "U$5") (pin "9") (pinfunction "GPIO2_9") (pintype "bidirectional"))
    )
    (net (code "37") (name "Net-(U$5-NTC)") (class "Default")
      (node (ref "R22") (pin "1") (pinfunction "1_1") (pintype "passive"))
      (node (ref "U$5") (pin "18") (pinfunction "NTC_18") (pintype "bidirectional"))
    )
    (net (code "38") (name "Net-(U$5-PVSS1)") (class "Default")
      (node (ref "C1") (pin "2") (pinfunction "2_2") (pintype "passive"))
      (node (ref "C8") (pin "2") (pinfunction "2_2") (pintype "passive"))
      (node (ref "R24") (pin "2") (pinfunction "2_2") (pintype "passive"))
      (node (ref "U$5") (pin "2") (pinfunction "PVSS1_2") (pintype "bidirectional"))
    )
    (net (code "39") (name "Net-(U$5-PVSS2)") (class "Default")
      (node (ref "C17") (pin "2") (pinfunction "2_2") (pintype "passive"))
      (node (ref "C3") (pin "2") (pinfunction "2_2") (pintype "passive"))
      (node (ref "R23") (pin "2") (pinfunction "2_2") (pintype "passive"))
      (node (ref "U$5") (pin "6") (pinfunction "PVSS2_6") (pintype "bidirectional"))
    )
    (net (code "40") (name "Net-(U$5-SHPHLD)") (class "Default")
      (node (ref "R25") (pin "1") (pinfunction "1_1") (pintype "passive"))
      (node (ref "U$5") (pin "15") (pinfunction "SHPHLD_15") (pintype "bidirectional"))
    )
    (net (code "41") (name "Net-(U$5-SW1)") (class "Default")
      (node (ref "U$2") (pin "1") (pinfunction "1_1") (pintype "passive"))
      (node (ref "U$5") (pin "3") (pinfunction "SW1_3") (pintype "bidirectional"))
    )
    (net (code "42") (name "Net-(U$5-SW2)") (class "Default")
      (node (ref "U$3") (pin "1") (pinfunction "1_1") (pintype "passive"))
      (node (ref "U$5") (pin "5") (pinfunction "SW2_5") (pintype "bidirectional"))
    )
    (net (code "43") (name "Net-(U$5-VBAT)") (class "Default")
      (node (ref "BAT+1") (pin "TP") (pinfunction "TP_TP") (pintype "input"))
      (node (ref "C19") (pin "1") (pinfunction "1_1") (pintype "passive"))
      (node (ref "U$5") (pin "19") (pinfunction "VBAT_19") (pintype "bidirectional"))
    )
    (net (code "44") (name "Net-(U$5-VSET1)") (class "Default")
      (node (ref "R17") (pin "2") (pinfunction "2_2") (pintype "passive"))
      (node (ref "U$5") (pin "17") (pinfunction "VSET1_17") (pintype "bidirectional"))
    )
    (net (code "45") (name "Net-(U$5-VSET2)") (class "Default")
      (node (ref "R21") (pin "2") (pinfunction "2_2") (pintype "passive"))
      (node (ref "U$5") (pin "16") (pinfunction "VSET2_16") (pintype "bidirectional"))
    )
    (net (code "46") (name "Net-(U$22-LEDK1)") (class "Default")
      (node (ref "R5") (pin "2") (pinfunction "2_2") (pintype "passive"))
      (node (ref "U$22") (pin "11") (pinfunction "LEDK2_11") (pintype "bidirectional"))
      (node (ref "U$22") (pin "12") (pinfunction "LEDK1_12") (pintype "bidirectional"))
    )
    (net (code "47") (name "Net-(U$35-VCC)") (class "Default")
      (node (ref "C24") (pin "1") (pinfunction "1_1") (pintype "passive"))
      (node (ref "C25") (pin "1") (pinfunction "1_1") (pintype "passive"))
      (node (ref "C7") (pin "1") (pinfunction "1_1") (pintype "passive"))
      (node (ref "JMP4") (pin "2") (pinfunction "2_2") (pintype "passive"))
      (node (ref "U$35") (pin "8") (pinfunction "VCC_8") (pintype "bidirectional"))
    )
    (net (code "48") (name "Net-(U2-CLKOE)") (class "Default")
      (node (ref "R18") (pin "1") (pinfunction "1_1") (pintype "passive"))
      (node (ref "R20") (pin "2") (pinfunction "2_2") (pintype "passive"))
      (node (ref "U2") (pin "3") (pinfunction "CLKOE_3") (pintype "input"))
    )
    (net (code "49") (name "Net-(U4-SEL)") (class "Default")
      (node (ref "R13") (pin "2") (pinfunction "2_2") (pintype "passive"))
      (node (ref "R6") (pin "2") (pinfunction "2_2") (pintype "passive"))
      (node (ref "U4") (pin "15") (pinfunction "SEL_15") (pintype "passive"))
    )
    (net (code "50") (name "Net-(U4-~{EN})") (class "Default")
      (node (ref "JMP1") (pin "2") (pinfunction "2_2") (pintype "passive"))
      (node (ref "U4") (pin "13") (pinfunction "~{EN}_13") (pintype "passive"))
    )
    (net (code "51") (name "PPG_POWER") (class "Default")
      (node (ref "J4") (pin "1") (pinfunction "1_1") (pintype "passive"))
      (node (ref "J4") (pin "3") (pinfunction "3_3") (pintype "passive"))
      (node (ref "Q2") (pin "3") (pinfunction "D_3") (pintype "passive"))
    )
    (net (code "52") (name "QSPI-0") (class "Default")
      (node (ref "MDBT1") (pin "21") (pinfunction "P0.13/QSPI0_21") (pintype "bidirectional"))
      (node (ref "U$35") (pin "5") (pinfunction "DI(IO0)_5") (pintype "bidirectional"))
    )
    (net (code "53") (name "QSPI-1") (class "Default")
      (node (ref "MDBT1") (pin "27") (pinfunction "P0.14/QSPI1_27") (pintype "bidirectional"))
      (node (ref "U$35") (pin "2") (pinfunction "DO(IO1)_2") (pintype "bidirectional"))
    )
    (net (code "54") (name "QSPI-2") (class "Default")
      (node (ref "MDBT1") (pin "23") (pinfunction "P0.15/QSPI2_23") (pintype "bidirectional"))
      (node (ref "U$35") (pin "3") (pinfunction "WP(IO2)_3") (pintype "bidirectional"))
    )
    (net (code "55") (name "QSPI-3") (class "Default")
      (node (ref "MDBT1") (pin "28") (pinfunction "P0.16/QSPI3_28") (pintype "bidirectional"))
      (node (ref "U$35") (pin "7") (pinfunction "/HOLD(IO3)_7") (pintype "bidirectional"))
    )
    (net (code "56") (name "QSPI-CLK") (class "Default")
      (node (ref "MDBT1") (pin "26") (pinfunction "P0.17/QSPI_SCK_26") (pintype "bidirectional"))
      (node (ref "U$35") (pin "6") (pinfunction "CLK_6") (pintype "bidirectional"))
    )
    (net (code "57") (name "QSPI-CS") (class "Default")
      (node (ref "MDBT1") (pin "16") (pinfunction "P0.18/QSPI_CSN_16") (pintype "bidirectional"))
      (node (ref "U$35") (pin "1") (pinfunction "/CS_1") (pintype "bidirectional"))
    )
    (net (code "58") (name "RESET1") (class "Default")
      (node (ref "MDBT1") (pin "6") (pinfunction "RESET_6") (pintype "bidirectional"))
      (node (ref "P1") (pin "TP") (pinfunction "TP_TP") (pintype "input"))
    )
    (net (code "59") (name "RTC_INT") (class "Default")
      (node (ref "MDBT1") (pin "35") (pinfunction "P0.06/AIN2_35") (pintype "bidirectional"))
      (node (ref "R12") (pin "1") (pinfunction "1_1") (pintype "passive"))
      (node (ref "U2") (pin "4") (pinfunction "~{INT}_4") (pintype "output"))
    )
    (net (code "60") (name "SBU") (class "Default")
      (node (ref "D8") (pin "C") (pinfunction "C_C") (pintype "passive"))
      (node (ref "R2") (pin "2") (pinfunction "2_2") (pintype "passive"))
      (node (ref "R4") (pin "2") (pinfunction "2_2") (pintype "passive"))
    )
    (net (code "61") (name "SDO") (class "Default")
      (node (ref "U$22") (pin "6") (pinfunction "SDO_6") (pintype "bidirectional"))
    )
    (net (code "62") (name "SENSOR_BRD_SUPPLY") (class "Default")
      (node (ref "C20") (pin "1") (pinfunction "1_1") (pintype "passive"))
      (node (ref "C21") (pin "1") (pinfunction "1_1") (pintype "passive"))
      (node (ref "J3") (pin "1") (pinfunction "1_1") (pintype "passive"))
      (node (ref "J3") (pin "3") (pinfunction "3_3") (pintype "passive"))
      (node (ref "J3") (pin "5") (pinfunction "5_5") (pintype "passive"))
      (node (ref "J4") (pin "5") (pinfunction "5_5") (pintype "passive"))
      (node (ref "J4") (pin "7") (pinfunction "7_7") (pintype "passive"))
      (node (ref "J4") (pin "9") (pinfunction "9_9") (pintype "passive"))
      (node (ref "U$5") (pin "29") (pinfunction "LSOUT1/VOUTLDO1_29") (pintype "bidirectional"))
    )
    (net (code "63") (name "SEN_MFIO") (class "Default")
      (node (ref "J3") (pin "16") (pinfunction "16_16") (pintype "passive"))
      (node (ref "MDBT1") (pin "63") (pinfunction "P1.07_63") (pintype "bidirectional"))
    )
    (net (code "64") (name "SEN_MISO") (class "Default")
      (node (ref "J3") (pin "15") (pinfunction "15_15") (pintype "passive"))
      (node (ref "MDBT1") (pin "18") (pinfunction "P0.10/HSPI_MISO_18") (pintype "bidirectional"))
    )
    (net (code "65") (name "SEN_MOSI") (class "Default")
      (node (ref "J3") (pin "8") (pinfunction "8_8") (pintype "passive"))
      (node (ref "MDBT1") (pin "19") (pinfunction "P0.09/HSPI_MOSI_19") (pintype "bidirectional"))
    )
    (net (code "66") (name "SEN_RST") (class "Default")
      (node (ref "J3") (pin "19") (pinfunction "19_19") (pintype "passive"))
      (node (ref "MDBT1") (pin "10") (pinfunction "P1.06_10") (pintype "bidirectional"))
    )
    (net (code "67") (name "SEN_SCK") (class "Default")
      (node (ref "J3") (pin "4") (pinfunction "4_4") (pintype "passive"))
      (node (ref "MDBT1") (pin "29") (pinfunction "P0.08/HSPI_SCK_29") (pintype "bidirectional"))
    )
    (net (code "68") (name "SEN_SCL") (class "Default")
      (node (ref "J3") (pin "18") (pinfunction "18_18") (pintype "passive"))
      (node (ref "MDBT1") (pin "9") (pinfunction "P0.25/AIN4_9") (pintype "bidirectional"))
      (node (ref "R33") (pin "2") (pinfunction "2_2") (pintype "passive"))
      (node (ref "U$5") (pin "14") (pinfunction "SCL_14") (pintype "bidirectional"))
      (node (ref "U2") (pin "7") (pinfunction "SCL_7") (pintype "input"))
      (node (ref "U3") (pin "13") (pinfunction "SCL_13") (pintype "bidirectional"))
    )
    (net (code "69") (name "SEN_SDA") (class "Default")
      (node (ref "J3") (pin "17") (pinfunction "17_17") (pintype "passive"))
      (node (ref "MDBT1") (pin "8") (pinfunction "P0.24_8") (pintype "bidirectional"))
      (node (ref "R30") (pin "2") (pinfunction "2_2") (pintype "passive"))
      (node (ref "U$5") (pin "13") (pinfunction "SDA_13") (pintype "bidirectional"))
      (node (ref "U2") (pin "8") (pinfunction "SDA_8") (pintype "bidirectional"))
      (node (ref "U3") (pin "14") (pinfunction "SDA_14") (pintype "bidirectional"))
    )
    (net (code "70") (name "SHPHLD") (class "Default")
      (node (ref "JMP3") (pin "3") (pinfunction "3_3") (pintype "passive"))
      (node (ref "R25") (pin "2") (pinfunction "2_2") (pintype "passive"))
    )
    (net (code "71") (name "SW1") (class "Default")
      (node (ref "JMP2") (pin "3") (pinfunction "3_3") (pintype "passive"))
      (node (ref "MDBT1") (pin "39") (pinfunction "P0.05/AIN1_39") (pintype "bidirectional"))
    )
    (net (code "72") (name "SW3") (class "Default")
      (node (ref "JMP3") (pin "1") (pinfunction "1_1") (pintype "passive"))
      (node (ref "MDBT1") (pin "30") (pinfunction "P0.03/NFC2_30") (pintype "bidirectional"))
    )
    (net (code "73") (name "SWCLK1") (class "Default")
      (node (ref "J1") (pin "3") (pinfunction "3_3") (pintype "passive"))
      (node (ref "MDBT1") (pin "2") (pinfunction "SWDCLK_2") (pintype "bidirectional"))
      (node (ref "U4") (pin "4") (pinfunction "S2B_4") (pintype "bidirectional"))
    )
    (net (code "74") (name "SWDIO1") (class "Default")
      (node (ref "J1") (pin "4") (pinfunction "4_4") (pintype "passive"))
      (node (ref "MDBT1") (pin "4") (pinfunction "SWDIO_4") (pintype "bidirectional"))
      (node (ref "U4") (pin "1") (pinfunction "S1B_1") (pintype "bidirectional"))
    )
    (net (code "75") (name "SW_D1") (class "Default")
      (node (ref "D11") (pin "2") (pinfunction "2_2") (pintype "bidirectional"))
      (node (ref "J2") (pin "A2") (pinfunction "SSTXP1_A2") (pintype "bidirectional"))
      (node (ref "J2") (pin "B2") (pinfunction "SSTXP2_B2") (pintype "bidirectional"))
      (node (ref "U4") (pin "2") (pinfunction "D1_2") (pintype "bidirectional"))
    )
    (net (code "76") (name "SW_D2") (class "Default")
      (node (ref "D1") (pin "2") (pinfunction "2_2") (pintype "bidirectional"))
      (node (ref "J2") (pin "A3") (pinfunction "SSTXN1_A3") (pintype "bidirectional"))
      (node (ref "J2") (pin "B3") (pinfunction "SSTXN2_B3") (pintype "bidirectional"))
      (node (ref "U4") (pin "5") (pinfunction "D2_5") (pintype "bidirectional"))
    )
    (net (code "77") (name "SW_D3") (class "Default")
      (node (ref "D6") (pin "2") (pinfunction "2_2") (pintype "bidirectional"))
      (node (ref "J2") (pin "A11") (pinfunction "SSRXP2_A11") (pintype "bidirectional"))
      (node (ref "J2") (pin "B11") (pinfunction "SSRXP1_B11") (pintype "bidirectional"))
      (node (ref "U4") (pin "7") (pinfunction "D3_7") (pintype "bidirectional"))
    )
    (net (code "78") (name "SW_D4") (class "Default")
      (node (ref "D5") (pin "2") (pinfunction "2_2") (pintype "bidirectional"))
      (node (ref "J2") (pin "A10") (pinfunction "SSRXN2_A10") (pintype "bidirectional"))
      (node (ref "J2") (pin "B10") (pinfunction "SSRXN1_B10") (pintype "bidirectional"))
      (node (ref "U4") (pin "10") (pinfunction "D4_10") (pintype "bidirectional"))
    )
    (net (code "79") (name "S_INT") (class "Default")
      (node (ref "J4") (pin "8") (pinfunction "8_8") (pintype "passive"))
      (node (ref "U4") (pin "9") (pinfunction "S3A_9") (pintype "bidirectional"))
    )
    (net (code "80") (name "S_SCL") (class "Default")
      (node (ref "J4") (pin "6") (pinfunction "6_6") (pintype "passive"))
      (node (ref "U4") (pin "3") (pinfunction "S2A_3") (pintype "bidirectional"))
    )
    (net (code "81") (name "S_SDA") (class "Default")
      (node (ref "J4") (pin "4") (pinfunction "4_4") (pintype "passive"))
      (node (ref "U4") (pin "16") (pinfunction "S1A_16") (pintype "bidirectional"))
    )
    (net (code "82") (name "TFT_BL") (class "Default")
      (node (ref "MDBT1") (pin "22") (pinfunction "P1.05_22") (pintype "bidirectional"))
      (node (ref "R1") (pin "2") (pinfunction "2_2") (pintype "passive"))
    )
    (net (code "83") (name "TFT_CS") (class "Default")
      (node (ref "MDBT1") (pin "11") (pinfunction "P1.04_11") (pintype "bidirectional"))
      (node (ref "U$22") (pin "4") (pinfunction "CSX_4") (pintype "bidirectional"))
    )
    (net (code "84") (name "TFT_DC") (class "Default")
      (node (ref "MDBT1") (pin "43") (pinfunction "P1.01_43") (pintype "bidirectional"))
      (node (ref "U$22") (pin "8") (pinfunction "WRX/RS_8") (pintype "bidirectional"))
    )
    (net (code "85") (name "TFT_MOSI") (class "Default")
      (node (ref "MDBT1") (pin "51") (pinfunction "P1.13_51") (pintype "bidirectional"))
      (node (ref "U$22") (pin "7") (pinfunction "SDA_7") (pintype "bidirectional"))
    )
    (net (code "86") (name "TFT_RST") (class "Default")
      (node (ref "MDBT1") (pin "65") (pinfunction "P0.29_65") (pintype "bidirectional"))
      (node (ref "U$22") (pin "3") (pinfunction "RESET_3") (pintype "bidirectional"))
    )
    (net (code "87") (name "TFT_SCK") (class "Default")
      (node (ref "MDBT1") (pin "47") (pinfunction "P1.15_47") (pintype "bidirectional"))
      (node (ref "U$22") (pin "5") (pinfunction "DCX/SCL_5") (pintype "bidirectional"))
    )
    (net (code "88") (name "TP_INT") (class "Default")
      (node (ref "MDBT1") (pin "7") (pinfunction "P0.26/AIN5_7") (pintype "bidirectional"))
      (node (ref "U$22") (pin "16") (pinfunction "TP_INT_16") (pintype "bidirectional"))
    )
    (net (code "89") (name "TP_RST") (class "Default")
      (node (ref "MDBT1") (pin "5") (pinfunction "P0.27/AIN6_5") (pintype "bidirectional"))
      (node (ref "U$22") (pin "19") (pinfunction "TP_RST_19") (pintype "bidirectional"))
    )
    (net (code "90") (name "TP_SCL") (class "Default")
      (node (ref "MDBT1") (pin "31") (pinfunction "P1.03/TWI_31") (pintype "bidirectional"))
      (node (ref "R9") (pin "2") (pinfunction "2_2") (pintype "passive"))
      (node (ref "U$22") (pin "17") (pinfunction "TP_SCL_17") (pintype "bidirectional"))
    )
    (net (code "91") (name "TP_SDA") (class "Default")
      (node (ref "MDBT1") (pin "33") (pinfunction "P1.02/TWI_33") (pintype "bidirectional"))
      (node (ref "R11") (pin "2") (pinfunction "2_2") (pintype "passive"))
      (node (ref "U$22") (pin "18") (pinfunction "TP_SDA_18") (pintype "bidirectional"))
    )
    (net (code "92") (name "UART_TX") (class "Default")
      (node (ref "J1") (pin "2") (pinfunction "2_2") (pintype "power_in"))
      (node (ref "MDBT1") (pin "13") (pinfunction "P0.20_13") (pintype "bidirectional"))
      (node (ref "TX") (pin "TP") (pinfunction "TP_TP") (pintype "input"))
      (node (ref "U4") (pin "8") (pinfunction "S3B_8") (pintype "bidirectional"))
    )
    (net (code "93") (name "USB_D+") (class "Default")
      (node (ref "MDBT1") (pin "46") (pinfunction "D+_46") (pintype "bidirectional"))
      (node (ref "R31") (pin "2") (pinfunction "2_2") (pintype "passive"))
    )
    (net (code "94") (name "USB_D-") (class "Default")
      (node (ref "MDBT1") (pin "48") (pinfunction "D-_48") (pintype "bidirectional"))
      (node (ref "R32") (pin "2") (pinfunction "2_2") (pintype "passive"))
    )
    (net (code "95") (name "VBUS") (class "Default")
      (node (ref "MDBT1") (pin "44") (pinfunction "VBUS_44") (pintype "bidirectional"))
      (node (ref "U$5") (pin "22") (pinfunction "VBUSOUT_22") (pintype "bidirectional"))
    )
    (net (code "96") (name "VCC") (class "Default")
      (node (ref "C1") (pin "1") (pinfunction "1_1") (pintype "passive"))
      (node (ref "C3") (pin "1") (pinfunction "1_1") (pintype "passive"))
      (node (ref "C6") (pin "1") (pinfunction "1_1") (pintype "passive"))
      (node (ref "U$5") (pin "20") (pinfunction "VSYS_20") (pintype "bidirectional"))
      (node (ref "U$5") (pin "4") (pinfunction "PVDD_4") (pintype "bidirectional"))
    )
    (net (code "97") (name "VUSB2") (class "Default")
      (node (ref "C18") (pin "1") (pinfunction "1_1") (pintype "passive"))
      (node (ref "C5") (pin "1") (pinfunction "1_1") (pintype "passive"))
      (node (ref "J2") (pin "A4") (pinfunction "VBUS_A_A4") (pintype "power_in"))
      (node (ref "J2") (pin "A9") (pinfunction "VBUS_A_A9") (pintype "power_in"))
      (node (ref "J2") (pin "B4") (pinfunction "VBUS_B_B4") (pintype "power_in"))
      (node (ref "J2") (pin "B9") (pinfunction "VBUS_B_B9") (pintype "power_in"))
      (node (ref "Q2") (pin "1") (pinfunction "G_1") (pintype "passive"))
      (node (ref "R15") (pin "2") (pinfunction "2_2") (pintype "passive"))
      (node (ref "R6") (pin "1") (pinfunction "1_1") (pintype "passive"))
      (node (ref "U$5") (pin "21") (pinfunction "VBUS_21") (pintype "bidirectional"))
    )
    (net (code "98") (name "W_MFIO") (class "Default")
      (node (ref "J3") (pin "12") (pinfunction "12_12") (pintype "passive"))
      (node (ref "MDBT1") (pin "60") (pinfunction "P0.28/AIN7_60") (pintype "bidirectional"))
    )
    (net (code "99") (name "unconnected-(J3-Pad6)") (class "Default")
      (node (ref "J3") (pin "6") (pinfunction "6_6") (pintype "passive"))
    )
    (net (code "100") (name "unconnected-(J3-Pad7)") (class "Default")
      (node (ref "J3") (pin "7") (pinfunction "7_7") (pintype "passive"))
    )
    (net (code "101") (name "unconnected-(J3-Pad10)") (class "Default")
      (node (ref "J3") (pin "10") (pinfunction "10_10") (pintype "passive"))
    )
    (net (code "102") (name "unconnected-(J3-Pad13)") (class "Default")
      (node (ref "J3") (pin "13") (pinfunction "13_13") (pintype "passive"))
    )
    (net (code "103") (name "unconnected-(J4-Pad10)") (class "Default")
      (node (ref "J4") (pin "10") (pinfunction "10_10") (pintype "passive"))
    )
    (net (code "104") (name "unconnected-(J4-Pad11)") (class "Default")
      (node (ref "J4") (pin "11") (pinfunction "11_11") (pintype "passive"))
    )
    (net (code "105") (name "unconnected-(J4-Pad12)") (class "Default")
      (node (ref "J4") (pin "12") (pinfunction "12_12") (pintype "passive"))
    )
    (net (code "106") (name "unconnected-(J4-Pad13)") (class "Default")
      (node (ref "J4") (pin "13") (pinfunction "13_13") (pintype "passive"))
    )
    (net (code "107") (name "unconnected-(J4-Pad14)") (class "Default")
      (node (ref "J4") (pin "14") (pinfunction "14_14") (pintype "passive"))
    )
    (net (code "108") (name "unconnected-(MDBT1-P0.04{slash}AIN0-Pad37)") (class "Default")
      (node (ref "MDBT1") (pin "37") (pinfunction "P0.04/AIN0_37") (pintype "bidirectional"))
    )
    (net (code "109") (name "unconnected-(MDBT1-P0.11{slash}HSPI_CSN-Pad17)") (class "Default")
      (node (ref "MDBT1") (pin "17") (pinfunction "P0.11/HSPI_CSN_17") (pintype "bidirectional"))
    )
    (net (code "110") (name "unconnected-(MDBT1-P0.12{slash}HSPI_DCX-Pad15)") (class "Default")
      (node (ref "MDBT1") (pin "15") (pinfunction "P0.12/HSPI_DCX_15") (pintype "bidirectional"))
    )
    (net (code "111") (name "unconnected-(MDBT1-P0.22-Pad25)") (class "Default")
      (node (ref "MDBT1") (pin "25") (pinfunction "P0.22_25") (pintype "bidirectional"))
    )
    (net (code "112") (name "unconnected-(MDBT1-P0.23-Pad62)") (class "Default")
      (node (ref "MDBT1") (pin "62") (pinfunction "P0.23_62") (pintype "bidirectional"))
    )
    (net (code "113") (name "unconnected-(MDBT1-P0.30-Pad57)") (class "Default")
      (node (ref "MDBT1") (pin "57") (pinfunction "P0.30_57") (pintype "bidirectional"))
    )
    (net (code "114") (name "unconnected-(MDBT1-P0.31-Pad56)") (class "Default")
      (node (ref "MDBT1") (pin "56") (pinfunction "P0.31_56") (pintype "bidirectional"))
    )
    (net (code "115") (name "unconnected-(MDBT1-P1.00-Pad45)") (class "Default")
      (node (ref "MDBT1") (pin "45") (pinfunction "P1.00_45") (pintype "bidirectional"))
    )
    (net (code "116") (name "unconnected-(MDBT1-P1.12-Pad53)") (class "Default")
      (node (ref "MDBT1") (pin "53") (pinfunction "P1.12_53") (pintype "bidirectional"))
    )
    (net (code "117") (name "unconnected-(MDBT1-P1.14-Pad49)") (class "Default")
      (node (ref "MDBT1") (pin "49") (pinfunction "P1.14_49") (pintype "bidirectional"))
    )
    (net (code "118") (name "unconnected-(U$5-GPIO3-Pad10)") (class "Default")
      (node (ref "U$5") (pin "10") (pinfunction "GPIO3_10") (pintype "bidirectional"))
    )
    (net (code "119") (name "unconnected-(U$5-GPIO4-Pad11)") (class "Default")
      (node (ref "U$5") (pin "11") (pinfunction "GPIO4_11") (pintype "bidirectional"))
    )
    (net (code "120") (name "unconnected-(U$5-LED0-Pad25)") (class "Default")
      (node (ref "U$5") (pin "25") (pinfunction "LED0_25") (pintype "bidirectional"))
    )
    (net (code "121") (name "unconnected-(U$5-LED1-Pad26)") (class "Default")
      (node (ref "U$5") (pin "26") (pinfunction "LED1_26") (pintype "bidirectional"))
    )
    (net (code "122") (name "unconnected-(U$5-LED2-Pad27)") (class "Default")
      (node (ref "U$5") (pin "27") (pinfunction "LED2_27") (pintype "bidirectional"))
    )
    (net (code "123") (name "unconnected-(U$5-LSIN2{slash}VINLDO2-Pad30)") (class "Default")
      (node (ref "U$5") (pin "30") (pinfunction "LSIN2/VINLDO2_30") (pintype "bidirectional"))
    )
    (net (code "124") (name "unconnected-(U$5-LSOUT2{slash}VOUTLDO2-Pad31)") (class "Default")
      (node (ref "U$5") (pin "31") (pinfunction "LSOUT2/VOUTLDO2_31") (pintype "bidirectional"))
    )
    (net (code "125") (name "unconnected-(U$17-0-Pad1)") (class "Default")
      (node (ref "U$17") (pin "1") (pinfunction "0_1") (pintype "passive"))
    )
    (net (code "126") (name "unconnected-(U$17-1-Pad4)") (class "Default")
      (node (ref "U$17") (pin "4") (pinfunction "1_4") (pintype "passive"))
    )
    (net (code "127") (name "unconnected-(U$22-NC-Pad15)") (class "Default")
      (node (ref "U$22") (pin "15") (pinfunction "NC_15") (pintype "bidirectional"))
    )
    (net (code "128") (name "unconnected-(U$24-0-Pad1)") (class "Default")
      (node (ref "U$24") (pin "1") (pinfunction "0_1") (pintype "passive"))
    )
    (net (code "129") (name "unconnected-(U$24-1-Pad4)") (class "Default")
      (node (ref "U$24") (pin "4") (pinfunction "1_4") (pintype "passive"))
    )
    (net (code "130") (name "unconnected-(U2-CLKOUT-Pad6)") (class "Default")
      (node (ref "U2") (pin "6") (pinfunction "CLKOUT_6") (pintype "output"))
    )
    (net (code "131") (name "unconnected-(U2-NC-Pad1)") (class "Default")
      (node (ref "U2") (pin "1") (pinfunction "NC_1") (pintype "no_connect"))
    )
    (net (code "132") (name "unconnected-(U3-INT2-Pad9)") (class "Default")
      (node (ref "U3") (pin "9") (pinfunction "INT2_9") (pintype "bidirectional"))
    )
    (net (code "133") (name "unconnected-(U3-NC-Pad11)") (class "Default")
      (node (ref "U3") (pin "11") (pinfunction "NC_11") (pintype "bidirectional"))
    )
    (net (code "134") (name "unconnected-(U3-OCS-Pad10)") (class "Default")
      (node (ref "U3") (pin "10") (pinfunction "OCS_10") (pintype "bidirectional"))
    )
    (net (code "135") (name "unconnected-(U4-S4A-Pad12)") (class "Default")
      (node (ref "U4") (pin "12") (pinfunction "S4A_12") (pintype "bidirectional"))
    )
    (net (code "136") (name "unconnected-(U4-S4B-Pad11)") (class "Default")
      (node (ref "U4") (pin "11") (pinfunction "S4B_11") (pintype "bidirectional"))
    )
  )
)
